# mq-x.net
KiCad netlist of a schematic drawn in Altium Designer
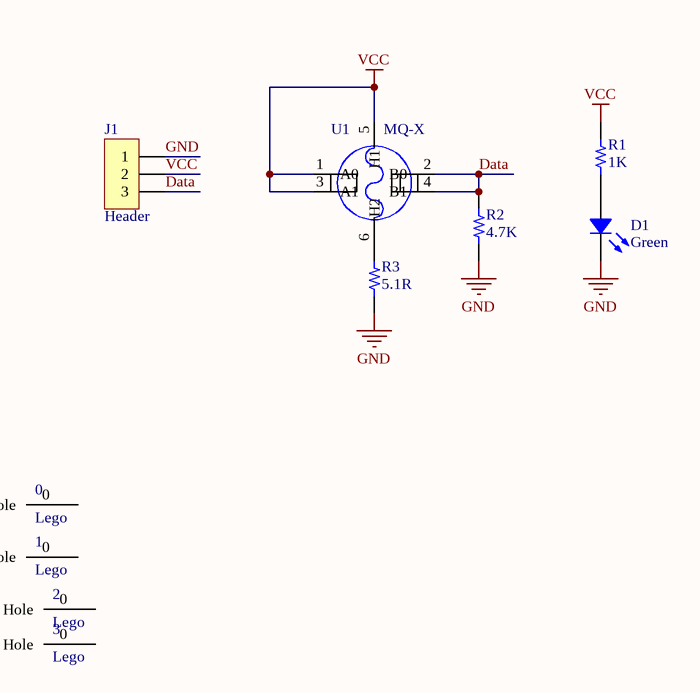
[diagram p0: mq-x.SchDoc]

(export (version "E")
  (design (tool "Eeschema 10.0.6"))
  (components
    (comp (ref "0") (value "Lego") (footprint "Lego Hole") (libsource (lib "Connectors") (part "Lego")))
    (comp (ref "1") (value "Lego") (footprint "Lego Hole") (libsource (lib "Connectors") (part "Lego")))
    (comp (ref "2") (value "Lego") (footprint "Lego Hole") (libsource (lib "Connectors") (part "Lego")))
    (comp (ref "3") (value "Lego") (footprint "Lego Hole") (libsource (lib "Connectors") (part "Lego")))
    (comp (ref "D1")
      (value "Green")
      (footprint "LED 1206/3216 RED")
      (description "Chip LED")
      (libsource (lib "Cap_Res") (part "LED"))
    )
    (comp (ref "J1")
      (value "Header")
      (footprint "MOLEX SDA-70553-3PIN")
      (libsource (lib "Connectors") (part "3 Pin"))
    )
    (comp (ref "R1")
      (value "1K")
      (footprint "RES 1206/3216")
      (description "SMT Resistor")
      (libsource (lib "Cap_Res") (part "Resistor"))
    )
    (comp (ref "R2")
      (value "4.7K")
      (footprint "RES 1206/3216")
      (description "SMT Resistor")
      (libsource (lib "Cap_Res") (part "Resistor"))
    )
    (comp (ref "R3")
      (value "5.1R")
      (footprint "RES 1206/3216")
      (description "SMT Resistor")
      (libsource (lib "Cap_Res") (part "Resistor"))
    )
    (comp (ref "U1")
      (value "MQ-X")
      (footprint "MQ-X")
      (fields (field (name "MF") "Mac8") (field (name "MP") "MQ9"))
      (libsource (lib "Sensors") (part "MQ-X"))
    )
  )
  (nets
    (net (code "1") (name "/Data") (class "Default")
      (node (ref "J1") (pin "3") (pinfunction "3_3") (pintype "passive"))
      (node (ref "R2") (pin "1") (pinfunction "1_1") (pintype "passive"))
      (node (ref "U1") (pin "2") (pinfunction "B0_2") (pintype "bidirectional"))
      (node (ref "U1") (pin "4") (pinfunction "B1_4") (pintype "bidirectional"))
    )
    (net (code "2") (name "GND") (class "Default")
      (node (ref "D1") (pin "2") (pinfunction "2_2") (pintype "passive"))
      (node (ref "J1") (pin "1") (pinfunction "1_1") (pintype "passive"))
      (node (ref "R2") (pin "2") (pinfunction "2_2") (pintype "passive"))
      (node (ref "R3") (pin "2") (pinfunction "2_2") (pintype "passive"))
    )
    (net (code "3") (name "Net-(D1-Pad1)") (class "Default")
      (node (ref "D1") (pin "1") (pinfunction "1_1") (pintype "passive"))
      (node (ref "R1") (pin "1") (pinfunction "1_1") (pintype "passive"))
    )
    (net (code "4") (name "Net-(U1-H2)") (class "Default")
      (node (ref "R3") (pin "1") (pinfunction "1_1") (pintype "passive"))
      (node (ref "U1") (pin "6") (pinfunction "H2_6") (pintype "bidirectional"))
    )
    (net (code "5") (name "VCC") (class "Default")
      (node (ref "J1") (pin "2") (pinfunction "2_2") (pintype "passive"))
      (node (ref "R1") (pin "2") (pinfunction "2_2") (pintype "passive"))
      (node (ref "U1") (pin "1") (pinfunction "A0_1") (pintype "bidirectional"))
      (node (ref "U1") (pin "3") (pinfunction "A1_3") (pintype "bidirectional"))
      (node (ref "U1") (pin "5") (pinfunction "H1_5") (pintype "bidirectional"))
    )
    (net (code "6") (name "unconnected-(0-Lego_Hole-Pad0)") (class "Default")
      (node (ref "0") (pin "0") (pinfunction "Lego_Hole_0") (pintype "passive"))
    )
    (net (code "7") (name "unconnected-(1-Lego_Hole-Pad0)") (class "Default")
      (node (ref "1") (pin "0") (pinfunction "Lego_Hole_0") (pintype "passive"))
    )
    (net (code "8") (name "unconnected-(2-Lego_Hole-Pad0)") (class "Default")
      (node (ref "2") (pin "0") (pinfunction "Lego_Hole_0") (pintype "passive"))
    )
    (net (code "9") (name "unconnected-(3-Lego_Hole-Pad0)") (class "Default")
      (node (ref "3") (pin "0") (pinfunction "Lego_Hole_0") (pintype "passive"))
    )
  )
)
